# USB_Hub.net
KiCad netlist of a schematic drawn in Altium Designer
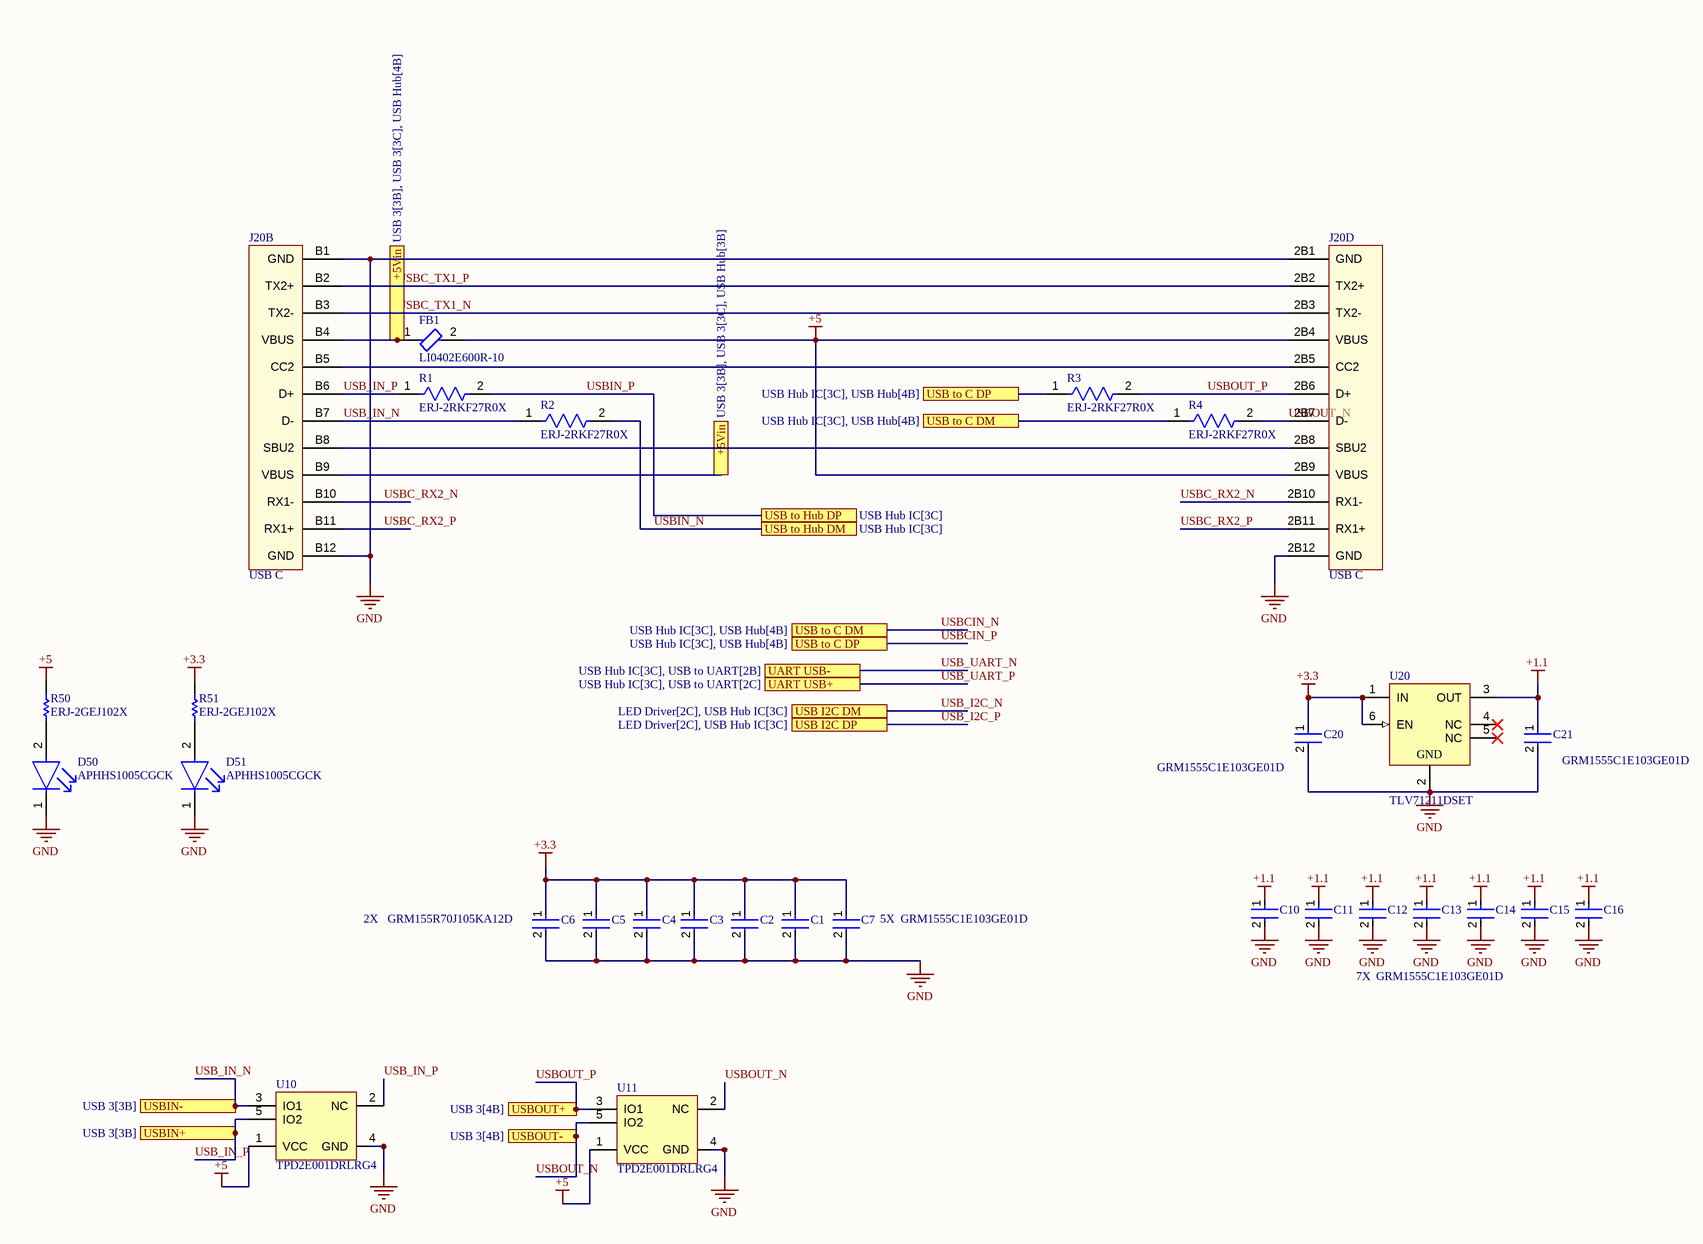
[diagram p0: USB Hub.SchDoc]

(export (version "E")
  (design (tool "Eeschema 10.0.6"))
  (components
    (comp (ref "C1")
      (value "GRM1555C1E103GE01D")
      (footprint "FP-GRM155-0_15-IPC_B")
      (description "Chip Multilayer Ceramic Capacitors for General Purpose, 0402, 10000pF, C0G, 30ppm/°C, 2%, 25V")
      (libsource (lib "Altium Content Vault") (part "b4654b650e69147ec39a6b967a45e02"))
    )
    (comp (ref "C2")
      (value "GRM1555C1E103GE01D")
      (footprint "FP-GRM155-0_15-IPC_B")
      (description "Chip Multilayer Ceramic Capacitors for General Purpose, 0402, 10000pF, C0G, 30ppm/°C, 2%, 25V")
      (libsource (lib "Altium Content Vault") (part "b4654b650e69147ec39a6b967a45e02"))
    )
    (comp (ref "C3")
      (value "GRM1555C1E103GE01D")
      (footprint "FP-GRM155-0_15-IPC_B")
      (description "Chip Multilayer Ceramic Capacitors for General Purpose, 0402, 10000pF, C0G, 30ppm/°C, 2%, 25V")
      (libsource (lib "Altium Content Vault") (part "b4654b650e69147ec39a6b967a45e02"))
    )
    (comp (ref "C4")
      (value "GRM1555C1E103GE01D")
      (footprint "FP-GRM155-0_15-IPC_B")
      (description "Chip Multilayer Ceramic Capacitors for General Purpose, 0402, 10000pF, C0G, 30ppm/°C, 2%, 25V")
      (libsource (lib "Altium Content Vault") (part "b4654b650e69147ec39a6b967a45e02"))
    )
    (comp (ref "C5")
      (value "GRM155R70J105KA12D")
      (footprint "FP-GRM155-0_05-MFG")
      (description "Chip Multilayer Ceramic Capacitors for General Purpose, 0402, 1.0uF, X7R, 15%, 10%, 6.3V")
      (fields (field (name "TOLERANCE") "10%"))
      (libsource (lib "Altium Content Vault") (part "02cd4be3c70576c341d710602a673aa"))
    )
    (comp (ref "C6")
      (value "GRM155R70J105KA12D")
      (footprint "FP-GRM155-0_05-MFG")
      (description "Chip Multilayer Ceramic Capacitors for General Purpose, 0402, 1.0uF, X7R, 15%, 10%, 6.3V")
      (fields (field (name "TOLERANCE") "10%"))
      (libsource (lib "Altium Content Vault") (part "02cd4be3c70576c341d710602a673aa"))
    )
    (comp (ref "C7")
      (value "GRM1555C1E103GE01D")
      (footprint "FP-GRM155-0_15-IPC_B")
      (description "Chip Multilayer Ceramic Capacitors for General Purpose, 0402, 10000pF, C0G, 30ppm/°C, 2%, 25V")
      (libsource (lib "Altium Content Vault") (part "b4654b650e69147ec39a6b967a45e02"))
    )
    (comp (ref "C10")
      (value "GRM1555C1E103GE01D")
      (footprint "FP-GRM155-0_15-IPC_B")
      (description "Chip Multilayer Ceramic Capacitors for General Purpose, 0402, 10000pF, C0G, 30ppm/°C, 2%, 25V")
      (libsource (lib "Altium Content Vault") (part "b4654b650e69147ec39a6b967a45e02"))
    )
    (comp (ref "C11")
      (value "GRM1555C1E103GE01D")
      (footprint "FP-GRM155-0_15-IPC_B")
      (description "Chip Multilayer Ceramic Capacitors for General Purpose, 0402, 10000pF, C0G, 30ppm/°C, 2%, 25V")
      (libsource (lib "Altium Content Vault") (part "b4654b650e69147ec39a6b967a45e02"))
    )
    (comp (ref "C12")
      (value "GRM1555C1E103GE01D")
      (footprint "FP-GRM155-0_15-IPC_B")
      (description "Chip Multilayer Ceramic Capacitors for General Purpose, 0402, 10000pF, C0G, 30ppm/°C, 2%, 25V")
      (libsource (lib "Altium Content Vault") (part "b4654b650e69147ec39a6b967a45e02"))
    )
    (comp (ref "C13")
      (value "GRM1555C1E103GE01D")
      (footprint "FP-GRM155-0_15-IPC_B")
      (description "Chip Multilayer Ceramic Capacitors for General Purpose, 0402, 10000pF, C0G, 30ppm/°C, 2%, 25V")
      (libsource (lib "Altium Content Vault") (part "b4654b650e69147ec39a6b967a45e02"))
    )
    (comp (ref "C14")
      (value "GRM1555C1E103GE01D")
      (footprint "FP-GRM155-0_15-IPC_B")
      (description "Chip Multilayer Ceramic Capacitors for General Purpose, 0402, 10000pF, C0G, 30ppm/°C, 2%, 25V")
      (libsource (lib "Altium Content Vault") (part "b4654b650e69147ec39a6b967a45e02"))
    )
    (comp (ref "C15")
      (value "GRM1555C1E103GE01D")
      (footprint "FP-GRM155-0_15-IPC_B")
      (description "Chip Multilayer Ceramic Capacitors for General Purpose, 0402, 10000pF, C0G, 30ppm/°C, 2%, 25V")
      (libsource (lib "Altium Content Vault") (part "b4654b650e69147ec39a6b967a45e02"))
    )
    (comp (ref "C16")
      (value "GRM1555C1E103GE01D")
      (footprint "FP-GRM155-0_15-IPC_B")
      (description "Chip Multilayer Ceramic Capacitors for General Purpose, 0402, 10000pF, C0G, 30ppm/°C, 2%, 25V")
      (libsource (lib "Altium Content Vault") (part "b4654b650e69147ec39a6b967a45e02"))
    )
    (comp (ref "C20")
      (value "GRM1555C1E103GE01D")
      (footprint "FP-GRM155-0_15-IPC_B")
      (description "Chip Multilayer Ceramic Capacitors for General Purpose, 0402, 10000pF, C0G, 30ppm/°C, 2%, 25V")
      (libsource (lib "Altium Content Vault") (part "b4654b650e69147ec39a6b967a45e02"))
    )
    (comp (ref "C21")
      (value "GRM1555C1E103GE01D")
      (footprint "FP-GRM155-0_15-IPC_B")
      (description "Chip Multilayer Ceramic Capacitors for General Purpose, 0402, 10000pF, C0G, 30ppm/°C, 2%, 25V")
      (libsource (lib "Altium Content Vault") (part "b4654b650e69147ec39a6b967a45e02"))
    )
    (comp (ref "D50")
      (value "APHHS1005CGCK")
      (footprint "FP-APHHS1005CGCK-MFG")
      (description "LED GREEN CLEAR CHIP SMD")
      (libsource (lib "Altium Content Vault") (part "8706943c75ba83719d021d2fdc84c58"))
    )
    (comp (ref "D51")
      (value "APHHS1005CGCK")
      (footprint "FP-APHHS1005CGCK-MFG")
      (description "LED GREEN CLEAR CHIP SMD")
      (libsource (lib "Altium Content Vault") (part "8706943c75ba83719d021d2fdc84c58"))
    )
    (comp (ref "FB1")
      (value "LI0402E600R-10")
      (footprint "FP-LI0402-MFG")
      (description "FERRITE BEAD 60 OHM 0402 1LN")
      (libsource (lib "Altium Content Vault") (part "5f30dd21d616792df468990f7003faa"))
    )
    (comp (ref "J20")
      (value "USB C")
      (footprint "Dual USB C Connector")
      (libsource (lib "") (part "USB C_1"))
    )
    (comp (ref "R1")
      (value "ERJ-2RKF27R0X")
      (footprint "FP-ERJ2R-IPC_B")
      (description "RES SMD 27 OHM 1% 1/10W 0402")
      (fields (field (name "TOLERANCE") "1%"))
      (libsource (lib "Altium Content Vault") (part "8db39607336c341a927600551d01821"))
    )
    (comp (ref "R2")
      (value "ERJ-2RKF27R0X")
      (footprint "FP-ERJ2R-IPC_B")
      (description "RES SMD 27 OHM 1% 1/10W 0402")
      (fields (field (name "TOLERANCE") "1%"))
      (libsource (lib "Altium Content Vault") (part "8db39607336c341a927600551d01821"))
    )
    (comp (ref "R3")
      (value "ERJ-2RKF27R0X")
      (footprint "FP-ERJ2R-IPC_B")
      (description "RES SMD 27 OHM 1% 1/10W 0402")
      (fields (field (name "TOLERANCE") "1%"))
      (libsource (lib "Altium Content Vault") (part "8db39607336c341a927600551d01821"))
    )
    (comp (ref "R4")
      (value "ERJ-2RKF27R0X")
      (footprint "FP-ERJ2R-IPC_B")
      (description "RES SMD 27 OHM 1% 1/10W 0402")
      (fields (field (name "TOLERANCE") "1%"))
      (libsource (lib "Altium Content Vault") (part "8db39607336c341a927600551d01821"))
    )
    (comp (ref "R50")
      (value "ERJ-2GEJ102X")
      (footprint "RESC1005X40X25NL05T05")
      (fields (field (name "MANUFACTURER") "Panasonic"))
      (libsource (lib "Altium Content Vault") (part "RES"))
    )
    (comp (ref "R51")
      (value "ERJ-2GEJ102X")
      (footprint "RESC1005X40X25NL05T05")
      (fields (field (name "MANUFACTURER") "Panasonic"))
      (libsource (lib "Altium Content Vault") (part "RES"))
    )
    (comp (ref "U10")
      (value "TPD2E001DRLRG4")
      (footprint "DRL0005A_L")
      (fields (field (name "MANUFACTURER") "Texas Instruments"))
      (libsource (lib "Altium Content Vault") (part "TI-TPD2E001-SOT_DRL-5"))
    )
    (comp (ref "U11")
      (value "TPD2E001DRLRG4")
      (footprint "DRL0005A_L")
      (fields (field (name "MANUFACTURER") "Texas Instruments"))
      (libsource (lib "Altium Content Vault") (part "TI-TPD2E001-SOT_DRL-5"))
    )
    (comp (ref "U20")
      (value "TLV71211DSET")
      (footprint "DSE0006A_V")
      (fields (field (name "MANUFACTURER") "Texas Instruments"))
      (libsource (lib "Altium Content Vault") (part "TI-TLV7XXXXDSE6"))
    )
  )
  (nets
    (net (code "1") (name "+1.1") (class "Default")
      (node (ref "C10") (pin "1") (pinfunction "1_1") (pintype "passive"))
      (node (ref "C11") (pin "1") (pinfunction "1_1") (pintype "passive"))
      (node (ref "C12") (pin "1") (pinfunction "1_1") (pintype "passive"))
      (node (ref "C13") (pin "1") (pinfunction "1_1") (pintype "passive"))
      (node (ref "C14") (pin "1") (pinfunction "1_1") (pintype "passive"))
      (node (ref "C15") (pin "1") (pinfunction "1_1") (pintype "passive"))
      (node (ref "C16") (pin "1") (pinfunction "1_1") (pintype "passive"))
      (node (ref "C21") (pin "1") (pinfunction "1_1") (pintype "passive"))
      (node (ref "U20") (pin "3") (pinfunction "OUT_3") (pintype "power_in"))
    )
    (net (code "2") (name "+3.3") (class "Default")
      (node (ref "C1") (pin "1") (pinfunction "1_1") (pintype "passive"))
      (node (ref "C2") (pin "1") (pinfunction "1_1") (pintype "passive"))
      (node (ref "C20") (pin "1") (pinfunction "1_1") (pintype "passive"))
      (node (ref "C3") (pin "1") (pinfunction "1_1") (pintype "passive"))
      (node (ref "C4") (pin "1") (pinfunction "1_1") (pintype "passive"))
      (node (ref "C5") (pin "1") (pinfunction "1_1") (pintype "passive"))
      (node (ref "C6") (pin "1") (pinfunction "1_1") (pintype "passive"))
      (node (ref "C7") (pin "1") (pinfunction "1_1") (pintype "passive"))
      (node (ref "R51") (pin "2") (pinfunction "2_2") (pintype "passive"))
      (node (ref "U20") (pin "1") (pinfunction "IN_1") (pintype "power_in"))
      (node (ref "U20") (pin "6") (pinfunction "EN_6") (pintype "input"))
    )
    (net (code "3") (name "+5") (class "Default")
      (node (ref "FB1") (pin "2") (pinfunction "2_2") (pintype "passive"))
      (node (ref "J20") (pin "2B4") (pinfunction "VBUS_2B4") (pintype "passive"))
      (node (ref "J20") (pin "2B9") (pinfunction "VBUS_2B9") (pintype "passive"))
      (node (ref "R50") (pin "2") (pinfunction "2_2") (pintype "passive"))
      (node (ref "U10") (pin "1") (pinfunction "VCC_1") (pintype "power_in"))
      (node (ref "U11") (pin "1") (pinfunction "VCC_1") (pintype "power_in"))
    )
    (net (code "4") (name "/+5Vin") (class "Default")
      (node (ref "FB1") (pin "1") (pinfunction "1_1") (pintype "passive"))
      (node (ref "J20") (pin "B4") (pinfunction "VBUS_B4") (pintype "passive"))
      (node (ref "J20") (pin "B9") (pinfunction "VBUS_B9") (pintype "passive"))
    )
    (net (code "5") (name "/USBCIN_N") (class "Default")
      (node (ref "R4") (pin "1") (pinfunction "1_1") (pintype "passive"))
    )
    (net (code "6") (name "/USBCIN_P") (class "Default")
      (node (ref "R3") (pin "1") (pinfunction "1_1") (pintype "passive"))
    )
    (net (code "7") (name "/USBC_RX2_N") (class "Default")
      (node (ref "J20") (pin "2B10") (pinfunction "RX1-_2B10") (pintype "passive"))
      (node (ref "J20") (pin "B10") (pinfunction "RX1-_B10") (pintype "passive"))
    )
    (net (code "8") (name "/USBC_RX2_P") (class "Default")
      (node (ref "J20") (pin "2B11") (pinfunction "RX1+_2B11") (pintype "passive"))
      (node (ref "J20") (pin "B11") (pinfunction "RX1+_B11") (pintype "passive"))
    )
    (net (code "9") (name "/USBC_TX1_N") (class "Default")
      (node (ref "J20") (pin "2B3") (pinfunction "TX2-_2B3") (pintype "passive"))
      (node (ref "J20") (pin "B3") (pinfunction "TX2-_B3") (pintype "passive"))
    )
    (net (code "10") (name "/USBC_TX1_P") (class "Default")
      (node (ref "J20") (pin "2B2") (pinfunction "TX2+_2B2") (pintype "passive"))
      (node (ref "J20") (pin "B2") (pinfunction "TX2+_B2") (pintype "passive"))
    )
    (net (code "11") (name "/USBIN_N") (class "Default")
      (node (ref "R2") (pin "2") (pinfunction "2_2") (pintype "passive"))
    )
    (net (code "12") (name "/USBIN_P") (class "Default")
      (node (ref "R1") (pin "2") (pinfunction "2_2") (pintype "passive"))
    )
    (net (code "13") (name "/USBOUT_N") (class "Default")
      (node (ref "J20") (pin "2B7") (pinfunction "D-_2B7") (pintype "passive"))
      (node (ref "R4") (pin "2") (pinfunction "2_2") (pintype "passive"))
      (node (ref "U11") (pin "2") (pinfunction "NC_2") (pintype "passive"))
      (node (ref "U11") (pin "5") (pinfunction "IO2_5") (pintype "passive"))
    )
    (net (code "14") (name "/USBOUT_P") (class "Default")
      (node (ref "J20") (pin "2B6") (pinfunction "D+_2B6") (pintype "passive"))
      (node (ref "R3") (pin "2") (pinfunction "2_2") (pintype "passive"))
      (node (ref "U11") (pin "3") (pinfunction "IO1_3") (pintype "passive"))
    )
    (net (code "17") (name "/USB_IN_N") (class "Default")
      (node (ref "J20") (pin "B7") (pinfunction "D-_B7") (pintype "passive"))
      (node (ref "R2") (pin "1") (pinfunction "1_1") (pintype "passive"))
      (node (ref "U10") (pin "3") (pinfunction "IO1_3") (pintype "passive"))
    )
    (net (code "18") (name "/USB_IN_P") (class "Default")
      (node (ref "J20") (pin "B6") (pinfunction "D+_B6") (pintype "passive"))
      (node (ref "R1") (pin "1") (pinfunction "1_1") (pintype "passive"))
      (node (ref "U10") (pin "2") (pinfunction "NC_2") (pintype "passive"))
      (node (ref "U10") (pin "5") (pinfunction "IO2_5") (pintype "passive"))
    )
    (net (code "21") (name "GND") (class "Default")
      (node (ref "C1") (pin "2") (pinfunction "2_2") (pintype "passive"))
      (node (ref "C10") (pin "2") (pinfunction "2_2") (pintype "passive"))
      (node (ref "C11") (pin "2") (pinfunction "2_2") (pintype "passive"))
      (node (ref "C12") (pin "2") (pinfunction "2_2") (pintype "passive"))
      (node (ref "C13") (pin "2") (pinfunction "2_2") (pintype "passive"))
      (node (ref "C14") (pin "2") (pinfunction "2_2") (pintype "passive"))
      (node (ref "C15") (pin "2") (pinfunction "2_2") (pintype "passive"))
      (node (ref "C16") (pin "2") (pinfunction "2_2") (pintype "passive"))
      (node (ref "C2") (pin "2") (pinfunction "2_2") (pintype "passive"))
      (node (ref "C20") (pin "2") (pinfunction "2_2") (pintype "passive"))
      (node (ref "C21") (pin "2") (pinfunction "2_2") (pintype "passive"))
      (node (ref "C3") (pin "2") (pinfunction "2_2") (pintype "passive"))
      (node (ref "C4") (pin "2") (pinfunction "2_2") (pintype "passive"))
      (node (ref "C5") (pin "2") (pinfunction "2_2") (pintype "passive"))
      (node (ref "C6") (pin "2") (pinfunction "2_2") (pintype "passive"))
      (node (ref "C7") (pin "2") (pinfunction "2_2") (pintype "passive"))
      (node (ref "D50") (pin "1") (pinfunction "C_1") (pintype "passive"))
      (node (ref "D51") (pin "1") (pinfunction "C_1") (pintype "passive"))
      (node (ref "J20") (pin "2B1") (pinfunction "GND_2B1") (pintype "passive"))
      (node (ref "J20") (pin "2B12") (pinfunction "GND_2B12") (pintype "passive"))
      (node (ref "J20") (pin "B1") (pinfunction "GND_B1") (pintype "passive"))
      (node (ref "J20") (pin "B12") (pinfunction "GND_B12") (pintype "passive"))
      (node (ref "U10") (pin "4") (pinfunction "GND_4") (pintype "power_in"))
      (node (ref "U11") (pin "4") (pinfunction "GND_4") (pintype "power_in"))
      (node (ref "U20") (pin "2") (pinfunction "GND_2") (pintype "power_in"))
    )
    (net (code "22") (name "Net-(D50-A)") (class "Default")
      (node (ref "D50") (pin "2") (pinfunction "A_2") (pintype "passive"))
      (node (ref "R50") (pin "1") (pinfunction "1_1") (pintype "passive"))
    )
    (net (code "23") (name "Net-(D51-A)") (class "Default")
      (node (ref "D51") (pin "2") (pinfunction "A_2") (pintype "passive"))
      (node (ref "R51") (pin "1") (pinfunction "1_1") (pintype "passive"))
    )
    (net (code "24") (name "Net-(J20B-CC2)") (class "Default")
      (node (ref "J20") (pin "2B5") (pinfunction "CC2_2B5") (pintype "passive"))
      (node (ref "J20") (pin "B5") (pinfunction "CC2_B5") (pintype "passive"))
    )
    (net (code "25") (name "Net-(J20B-SBU2)") (class "Default")
      (node (ref "J20") (pin "2B8") (pinfunction "SBU2_2B8") (pintype "passive"))
      (node (ref "J20") (pin "B8") (pinfunction "SBU2_B8") (pintype "passive"))
    )
    (net (code "26") (name "unconnected-(U20-NC-Pad4)") (class "Default")
      (node (ref "U20") (pin "4") (pinfunction "NC_4") (pintype "passive+no_connect"))
    )
    (net (code "27") (name "unconnected-(U20-NC-Pad5)") (class "Default")
      (node (ref "U20") (pin "5") (pinfunction "NC_5") (pintype "passive+no_connect"))
    )
  )
)
